# pcb_bobinadora.net
KiCad netlist of a schematic drawn in EAGLE
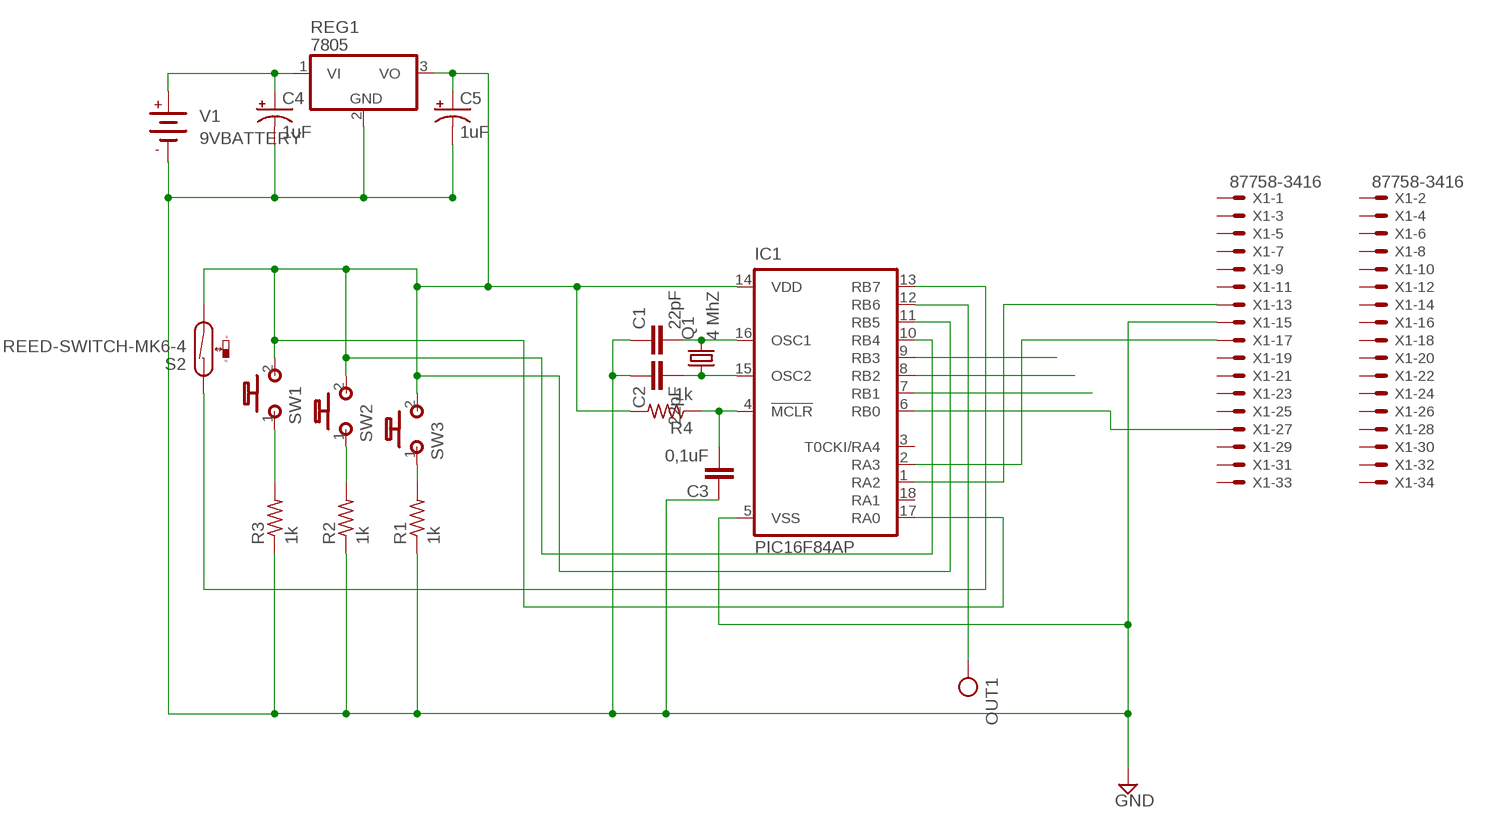
[diagram p0: schematic, sheet 1]

(export (version "E")
  (design (tool "Eeschema 10.0.6"))
  (components
    (comp (ref "C1")
      (value "22pF")
      (footprint "eagle-import:050X030_025")
      (libsource (lib "eagle-import") (part "050X030_0251"))
    )
    (comp (ref "C2")
      (value "22pF")
      (footprint "eagle-import:050X030_025")
      (libsource (lib "eagle-import") (part "050X030_0251"))
    )
    (comp (ref "C3")
      (value "0,1uF")
      (footprint "eagle-import:050X030_025")
      (libsource (lib "eagle-import") (part "050X030_0251"))
    )
    (comp (ref "C4")
      (value "1uF")
      (footprint "eagle-import:050_020")
      (libsource (lib "eagle-import") (part "050"))
    )
    (comp (ref "C5")
      (value "1uF")
      (footprint "eagle-import:050_020")
      (libsource (lib "eagle-import") (part "050"))
    )
    (comp (ref "IC1")
      (value "PIC16F84AP")
      (footprint "eagle-import:DIL18")
      (fields (field (name "MF") "MICROCHIP") (field (name "MPN") "PIC16F84A-04I/P"))
      (libsource (lib "eagle-import") (part "PIC16F8P4A"))
    )
    (comp (ref "OUT1")
      (value "OUT(T)")
      (footprint "eagle-import:SQUARE")
      (libsource (lib "eagle-import") (part "OUT(T)"))
    )
    (comp (ref "Q1")
      (value "4 MhZ")
      (footprint "eagle-import:HC18U-V")
      (libsource (lib "eagle-import") (part "CRYSTALHC18U-V"))
    )
    (comp (ref "R1")
      (value "1k")
      (footprint "eagle-import:R0207_4")
      (libsource (lib "eagle-import") (part "6MM.4"))
    )
    (comp (ref "R2")
      (value "1k")
      (footprint "eagle-import:R0207_4")
      (libsource (lib "eagle-import") (part "6MM.4"))
    )
    (comp (ref "R3")
      (value "1k")
      (footprint "eagle-import:R0207_4")
      (libsource (lib "eagle-import") (part "6MM.4"))
    )
    (comp (ref "R4")
      (value "1k")
      (footprint "eagle-import:R0207_4")
      (libsource (lib "eagle-import") (part "6MM.4"))
    )
    (comp (ref "REG1")
      (value "7805")
      (footprint "eagle-import:TO92-")
      (libsource (lib "eagle-import") (part "7805"))
    )
    (comp (ref "S2")
      (value "REED-SWITCH-MK6-4")
      (footprint "eagle-import:MK6-4")
      (libsource (lib "eagle-import") (part "REED-SWITCH-MK6-4"))
    )
    (comp (ref "SW1")
      (value "MOMENTARY")
      (footprint "eagle-import:SPST")
      (libsource (lib "eagle-import") (part "MOMENTARY"))
    )
    (comp (ref "SW2")
      (value "MOMENTARY")
      (footprint "eagle-import:SPST")
      (libsource (lib "eagle-import") (part "MOMENTARY"))
    )
    (comp (ref "SW3")
      (value "MOMENTARY")
      (footprint "eagle-import:SPST")
      (libsource (lib "eagle-import") (part "MOMENTARY"))
    )
    (comp (ref "V1")
      (value "9VBATTERY")
      (footprint "eagle-import:AB9V")
      (libsource (lib "eagle-import") (part "9VBATTERY"))
    )
    (comp (ref "X1")
      (value "87758-3416")
      (footprint "eagle-import:87758-3416")
      (libsource (lib "eagle-import") (part "87758-3416"))
    )
  )
  (nets
    (net (code "1") (name "GND") (class "Default")
      (node (ref "C1") (pin "1") (pinfunction "1_1") (pintype "passive"))
      (node (ref "C2") (pin "1") (pinfunction "1_1") (pintype "passive"))
      (node (ref "C3") (pin "1") (pinfunction "1_1") (pintype "passive"))
      (node (ref "C4") (pin "-") (pinfunction "-_-") (pintype "passive"))
      (node (ref "C5") (pin "-") (pinfunction "-_-") (pintype "passive"))
      (node (ref "IC1") (pin "5") (pinfunction "VSS_5") (pintype "power_in"))
      (node (ref "R1") (pin "1") (pinfunction "1_1") (pintype "passive"))
      (node (ref "R2") (pin "1") (pinfunction "1_1") (pintype "passive"))
      (node (ref "R3") (pin "1") (pinfunction "1_1") (pintype "passive"))
      (node (ref "REG1") (pin "2") (pinfunction "GND_2") (pintype "passive"))
      (node (ref "V1") (pin "-") (pinfunction "-_-") (pintype "passive"))
      (node (ref "X1") (pin "15") (pinfunction "S_15") (pintype "passive"))
    )
    (net (code "2") (name "Net-(IC1-OSC1)") (class "Default")
      (node (ref "C1") (pin "2") (pinfunction "2_2") (pintype "passive"))
      (node (ref "IC1") (pin "16") (pinfunction "OSC1_16") (pintype "input"))
      (node (ref "Q1") (pin "2") (pinfunction "2_2") (pintype "passive"))
    )
    (net (code "3") (name "Net-(IC1-OSC2)") (class "Default")
      (node (ref "C2") (pin "2") (pinfunction "2_2") (pintype "passive"))
      (node (ref "IC1") (pin "15") (pinfunction "OSC2_15") (pintype "output"))
      (node (ref "Q1") (pin "1") (pinfunction "1_1") (pintype "passive"))
    )
    (net (code "4") (name "Net-(IC1-RA0)") (class "Default")
      (node (ref "C5") (pin "+") (pinfunction "+_+") (pintype "passive"))
      (node (ref "IC1") (pin "10") (pinfunction "RB4_10") (pintype "bidirectional"))
      (node (ref "IC1") (pin "11") (pinfunction "RB5_11") (pintype "bidirectional"))
      (node (ref "IC1") (pin "14") (pinfunction "VDD_14") (pintype "power_in"))
      (node (ref "IC1") (pin "17") (pinfunction "RA0_17") (pintype "bidirectional"))
      (node (ref "R4") (pin "2") (pinfunction "2_2") (pintype "passive"))
      (node (ref "REG1") (pin "3") (pinfunction "VO_3") (pintype "passive"))
      (node (ref "S2") (pin "2") (pinfunction "2_2") (pintype "passive"))
      (node (ref "SW1") (pin "2") (pinfunction "S_2") (pintype "passive"))
      (node (ref "SW2") (pin "2") (pinfunction "S_2") (pintype "passive"))
      (node (ref "SW3") (pin "2") (pinfunction "S_2") (pintype "passive"))
    )
    (net (code "5") (name "Net-(IC1-RA2)") (class "Default")
      (node (ref "IC1") (pin "1") (pinfunction "RA2_1") (pintype "bidirectional"))
      (node (ref "X1") (pin "13") (pinfunction "S_13") (pintype "passive"))
    )
    (net (code "6") (name "Net-(IC1-RA3)") (class "Default")
      (node (ref "IC1") (pin "2") (pinfunction "RA3_2") (pintype "bidirectional"))
      (node (ref "X1") (pin "17") (pinfunction "S_17") (pintype "passive"))
    )
    (net (code "7") (name "Net-(IC1-RB0)") (class "Default")
      (node (ref "IC1") (pin "6") (pinfunction "RB0_6") (pintype "bidirectional"))
      (node (ref "X1") (pin "27") (pinfunction "S_27") (pintype "passive"))
    )
    (net (code "8") (name "Net-(IC1-RB7)") (class "Default")
      (node (ref "IC1") (pin "13") (pinfunction "RB7_13") (pintype "bidirectional"))
      (node (ref "S2") (pin "1") (pinfunction "1_1") (pintype "passive"))
    )
    (net (code "9") (name "Net-(IC1-~{MCLR})") (class "Default")
      (node (ref "C3") (pin "2") (pinfunction "2_2") (pintype "passive"))
      (node (ref "IC1") (pin "4") (pinfunction "~{MCLR}_4") (pintype "input"))
      (node (ref "R4") (pin "1") (pinfunction "1_1") (pintype "passive"))
    )
    (net (code "10") (name "Net-(REG1-VI)") (class "Default")
      (node (ref "C4") (pin "+") (pinfunction "+_+") (pintype "passive"))
      (node (ref "REG1") (pin "1") (pinfunction "VI_1") (pintype "input"))
      (node (ref "V1") (pin "+") (pinfunction "+_+") (pintype "passive"))
    )
    (net (code "11") (name "Net-(SW1-P)") (class "Default")
      (node (ref "R3") (pin "2") (pinfunction "2_2") (pintype "passive"))
      (node (ref "SW1") (pin "1") (pinfunction "P_1") (pintype "passive"))
    )
    (net (code "12") (name "Net-(SW2-P)") (class "Default")
      (node (ref "R2") (pin "2") (pinfunction "2_2") (pintype "passive"))
      (node (ref "SW2") (pin "1") (pinfunction "P_1") (pintype "passive"))
    )
    (net (code "13") (name "Net-(SW3-P)") (class "Default")
      (node (ref "R1") (pin "2") (pinfunction "2_2") (pintype "passive"))
      (node (ref "SW3") (pin "1") (pinfunction "P_1") (pintype "passive"))
    )
    (net (code "14") (name "OUT(T)") (class "Default")
      (node (ref "IC1") (pin "12") (pinfunction "RB6_12") (pintype "bidirectional"))
      (node (ref "OUT1") (pin "1") (pinfunction "OUT_1") (pintype "power_in"))
    )
    (net (code "15") (name "unconnected-(IC1-RA1-Pad18)") (class "Default")
      (node (ref "IC1") (pin "18") (pinfunction "RA1_18") (pintype "bidirectional"))
    )
    (net (code "16") (name "unconnected-(IC1-RB1-Pad7)") (class "Default")
      (node (ref "IC1") (pin "7") (pinfunction "RB1_7") (pintype "bidirectional"))
    )
    (net (code "17") (name "unconnected-(IC1-RB2-Pad8)") (class "Default")
      (node (ref "IC1") (pin "8") (pinfunction "RB2_8") (pintype "bidirectional"))
    )
    (net (code "18") (name "unconnected-(IC1-RB3-Pad9)") (class "Default")
      (node (ref "IC1") (pin "9") (pinfunction "RB3_9") (pintype "bidirectional"))
    )
    (net (code "19") (name "unconnected-(IC1-T0CKI{slash}RA4-Pad3)") (class "Default")
      (node (ref "IC1") (pin "3") (pinfunction "T0CKI/RA4_3") (pintype "bidirectional"))
    )
    (net (code "20") (name "unconnected-(X1A-S-Pad1)") (class "Default")
      (node (ref "X1") (pin "1") (pinfunction "S_1") (pintype "passive"))
    )
    (net (code "21") (name "unconnected-(X1AA-S-Pad33)") (class "Default")
      (node (ref "X1") (pin "33") (pinfunction "S_33") (pintype "passive"))
    )
    (net (code "22") (name "unconnected-(X1AB-S-Pad34)") (class "Default")
      (node (ref "X1") (pin "34") (pinfunction "S_34") (pintype "passive"))
    )
    (net (code "23") (name "unconnected-(X1AC-S-Pad4)") (class "Default")
      (node (ref "X1") (pin "4") (pinfunction "S_4") (pintype "passive"))
    )
    (net (code "24") (name "unconnected-(X1AD-S-Pad5)") (class "Default")
      (node (ref "X1") (pin "5") (pinfunction "S_5") (pintype "passive"))
    )
    (net (code "25") (name "unconnected-(X1AE-S-Pad6)") (class "Default")
      (node (ref "X1") (pin "6") (pinfunction "S_6") (pintype "passive"))
    )
    (net (code "26") (name "unconnected-(X1AF-S-Pad7)") (class "Default")
      (node (ref "X1") (pin "7") (pinfunction "S_7") (pintype "passive"))
    )
    (net (code "27") (name "unconnected-(X1AG-S-Pad8)") (class "Default")
      (node (ref "X1") (pin "8") (pinfunction "S_8") (pintype "passive"))
    )
    (net (code "28") (name "unconnected-(X1AH-S-Pad9)") (class "Default")
      (node (ref "X1") (pin "9") (pinfunction "S_9") (pintype "passive"))
    )
    (net (code "29") (name "unconnected-(X1B-S-Pad10)") (class "Default")
      (node (ref "X1") (pin "10") (pinfunction "S_10") (pintype "passive"))
    )
    (net (code "30") (name "unconnected-(X1C-S-Pad11)") (class "Default")
      (node (ref "X1") (pin "11") (pinfunction "S_11") (pintype "passive"))
    )
    (net (code "31") (name "unconnected-(X1D-S-Pad12)") (class "Default")
      (node (ref "X1") (pin "12") (pinfunction "S_12") (pintype "passive"))
    )
    (net (code "32") (name "unconnected-(X1F-S-Pad14)") (class "Default")
      (node (ref "X1") (pin "14") (pinfunction "S_14") (pintype "passive"))
    )
    (net (code "33") (name "unconnected-(X1H-S-Pad16)") (class "Default")
      (node (ref "X1") (pin "16") (pinfunction "S_16") (pintype "passive"))
    )
    (net (code "34") (name "unconnected-(X1J-S-Pad18)") (class "Default")
      (node (ref "X1") (pin "18") (pinfunction "S_18") (pintype "passive"))
    )
    (net (code "35") (name "unconnected-(X1K-S-Pad19)") (class "Default")
      (node (ref "X1") (pin "19") (pinfunction "S_19") (pintype "passive"))
    )
    (net (code "36") (name "unconnected-(X1L-S-Pad2)") (class "Default")
      (node (ref "X1") (pin "2") (pinfunction "S_2") (pintype "passive"))
    )
    (net (code "37") (name "unconnected-(X1M-S-Pad20)") (class "Default")
      (node (ref "X1") (pin "20") (pinfunction "S_20") (pintype "passive"))
    )
    (net (code "38") (name "unconnected-(X1N-S-Pad21)") (class "Default")
      (node (ref "X1") (pin "21") (pinfunction "S_21") (pintype "passive"))
    )
    (net (code "39") (name "unconnected-(X1O-S-Pad22)") (class "Default")
      (node (ref "X1") (pin "22") (pinfunction "S_22") (pintype "passive"))
    )
    (net (code "40") (name "unconnected-(X1P-S-Pad23)") (class "Default")
      (node (ref "X1") (pin "23") (pinfunction "S_23") (pintype "passive"))
    )
    (net (code "41") (name "unconnected-(X1Q-S-Pad24)") (class "Default")
      (node (ref "X1") (pin "24") (pinfunction "S_24") (pintype "passive"))
    )
    (net (code "42") (name "unconnected-(X1R-S-Pad25)") (class "Default")
      (node (ref "X1") (pin "25") (pinfunction "S_25") (pintype "passive"))
    )
    (net (code "43") (name "unconnected-(X1S-S-Pad26)") (class "Default")
      (node (ref "X1") (pin "26") (pinfunction "S_26") (pintype "passive"))
    )
    (net (code "44") (name "unconnected-(X1U-S-Pad28)") (class "Default")
      (node (ref "X1") (pin "28") (pinfunction "S_28") (pintype "passive"))
    )
    (net (code "45") (name "unconnected-(X1V-S-Pad29)") (class "Default")
      (node (ref "X1") (pin "29") (pinfunction "S_29") (pintype "passive"))
    )
    (net (code "46") (name "unconnected-(X1W-S-Pad3)") (class "Default")
      (node (ref "X1") (pin "3") (pinfunction "S_3") (pintype "passive"))
    )
    (net (code "47") (name "unconnected-(X1X-S-Pad30)") (class "Default")
      (node (ref "X1") (pin "30") (pinfunction "S_30") (pintype "passive"))
    )
    (net (code "48") (name "unconnected-(X1Y-S-Pad31)") (class "Default")
      (node (ref "X1") (pin "31") (pinfunction "S_31") (pintype "passive"))
    )
    (net (code "49") (name "unconnected-(X1Z-S-Pad32)") (class "Default")
      (node (ref "X1") (pin "32") (pinfunction "S_32") (pintype "passive"))
    )
  )
)
